# Sheet1.net
KiCad netlist of a schematic drawn in Altium Designer
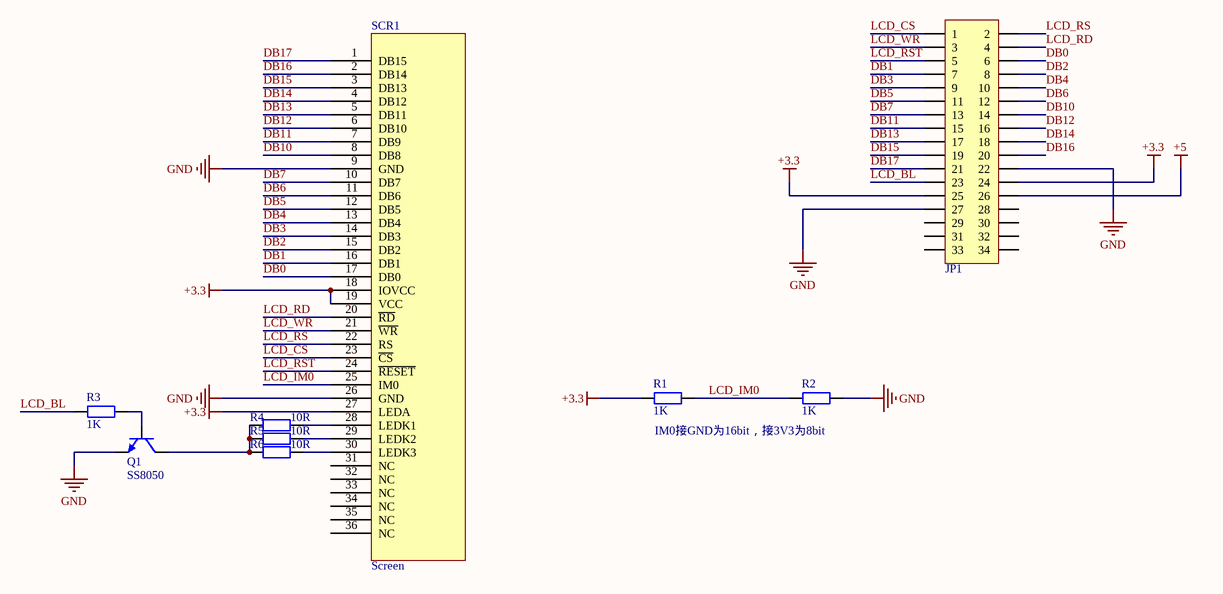
[diagram p0: Sheet1.SchDoc]

(export (version "E")
  (design (tool "Eeschema 10.0.6"))
  (components
    (comp (ref "JP1")
      (value "Header 2X11")
      (footprint "HDR2.54-LI-2x17P")
      (description "17*2P接插件")
      (libsource (lib "5.4 - 接插件-脚距2.54 (100mil) ") (part "Header 17X2"))
    )
    (comp (ref "Q1")
      (value "SS8050")
      (footprint "SOT23-3N")
      (description "高频放大-NPN型")
      (libsource (lib "0.4 - 三极管-场效应管-可控硅") (part "8050-SMD"))
    )
    (comp (ref "R1")
      (value "1K")
      (footprint "R 0603_L")
      (description "贴片电阻")
      (libsource (lib "0.1 - 电阻-电容-电感") (part "R"))
    )
    (comp (ref "R2")
      (value "1K")
      (footprint "R 0603_L")
      (description "贴片电阻")
      (libsource (lib "0.1 - 电阻-电容-电感") (part "R"))
    )
    (comp (ref "R3")
      (value "1K")
      (footprint "R 0603_L")
      (description "贴片电阻")
      (libsource (lib "0.1 - 电阻-电容-电感") (part "R"))
    )
    (comp (ref "R4")
      (value "10R")
      (footprint "R 0603_L")
      (description "贴片电阻")
      (libsource (lib "0.1 - 电阻-电容-电感") (part "R"))
    )
    (comp (ref "R5")
      (value "10R")
      (footprint "R 0603_L")
      (description "贴片电阻")
      (libsource (lib "0.1 - 电阻-电容-电感") (part "R"))
    )
    (comp (ref "R6")
      (value "10R")
      (footprint "R 0603_L")
      (description "贴片电阻")
      (libsource (lib "0.1 - 电阻-电容-电感") (part "R"))
    )
    (comp (ref "SCR1") (value "Screen") (footprint "2.0inLCD") (libsource (lib "Schlib1") (part "2.0inLCD")))
  )
  (nets
    (net (code "1") (name "+3.3") (class "Default")
      (node (ref "JP1") (pin "24") (pinfunction "24_24") (pintype "passive"))
      (node (ref "JP1") (pin "25") (pinfunction "25_25") (pintype "passive"))
      (node (ref "R1") (pin "1") (pinfunction "1_1") (pintype "passive"))
      (node (ref "SCR1") (pin "18") (pinfunction "IOVCC_18") (pintype "passive"))
      (node (ref "SCR1") (pin "19") (pinfunction "VCC_19") (pintype "passive"))
      (node (ref "SCR1") (pin "27") (pinfunction "LEDA_27") (pintype "passive"))
    )
    (net (code "2") (name "+5") (class "Default")
      (node (ref "JP1") (pin "26") (pinfunction "26_26") (pintype "passive"))
    )
    (net (code "3") (name "/DB0") (class "Default")
      (node (ref "JP1") (pin "6") (pinfunction "6_6") (pintype "passive"))
      (node (ref "SCR1") (pin "17") (pinfunction "DB0_17") (pintype "passive"))
    )
    (net (code "4") (name "/DB1") (class "Default")
      (node (ref "JP1") (pin "7") (pinfunction "7_7") (pintype "passive"))
      (node (ref "SCR1") (pin "16") (pinfunction "DB1_16") (pintype "passive"))
    )
    (net (code "5") (name "/DB2") (class "Default")
      (node (ref "JP1") (pin "8") (pinfunction "8_8") (pintype "passive"))
      (node (ref "SCR1") (pin "15") (pinfunction "DB2_15") (pintype "passive"))
    )
    (net (code "6") (name "/DB3") (class "Default")
      (node (ref "JP1") (pin "9") (pinfunction "9_9") (pintype "passive"))
      (node (ref "SCR1") (pin "14") (pinfunction "DB3_14") (pintype "passive"))
    )
    (net (code "7") (name "/DB4") (class "Default")
      (node (ref "JP1") (pin "10") (pinfunction "10_10") (pintype "passive"))
      (node (ref "SCR1") (pin "13") (pinfunction "DB4_13") (pintype "passive"))
    )
    (net (code "8") (name "/DB5") (class "Default")
      (node (ref "JP1") (pin "11") (pinfunction "11_11") (pintype "passive"))
      (node (ref "SCR1") (pin "12") (pinfunction "DB5_12") (pintype "passive"))
    )
    (net (code "9") (name "/DB6") (class "Default")
      (node (ref "JP1") (pin "12") (pinfunction "12_12") (pintype "passive"))
      (node (ref "SCR1") (pin "11") (pinfunction "DB6_11") (pintype "passive"))
    )
    (net (code "10") (name "/DB7") (class "Default")
      (node (ref "JP1") (pin "13") (pinfunction "13_13") (pintype "passive"))
      (node (ref "SCR1") (pin "10") (pinfunction "DB7_10") (pintype "passive"))
    )
    (net (code "11") (name "/DB10") (class "Default")
      (node (ref "JP1") (pin "14") (pinfunction "14_14") (pintype "passive"))
      (node (ref "SCR1") (pin "8") (pinfunction "DB8_8") (pintype "passive"))
    )
    (net (code "12") (name "/DB11") (class "Default")
      (node (ref "JP1") (pin "15") (pinfunction "15_15") (pintype "passive"))
      (node (ref "SCR1") (pin "7") (pinfunction "DB9_7") (pintype "passive"))
    )
    (net (code "13") (name "/DB12") (class "Default")
      (node (ref "JP1") (pin "16") (pinfunction "16_16") (pintype "passive"))
      (node (ref "SCR1") (pin "6") (pinfunction "DB10_6") (pintype "passive"))
    )
    (net (code "14") (name "/DB13") (class "Default")
      (node (ref "JP1") (pin "17") (pinfunction "17_17") (pintype "passive"))
      (node (ref "SCR1") (pin "5") (pinfunction "DB11_5") (pintype "passive"))
    )
    (net (code "15") (name "/DB14") (class "Default")
      (node (ref "JP1") (pin "18") (pinfunction "18_18") (pintype "passive"))
      (node (ref "SCR1") (pin "4") (pinfunction "DB12_4") (pintype "passive"))
    )
    (net (code "16") (name "/DB15") (class "Default")
      (node (ref "JP1") (pin "19") (pinfunction "19_19") (pintype "passive"))
      (node (ref "SCR1") (pin "3") (pinfunction "DB13_3") (pintype "passive"))
    )
    (net (code "17") (name "/DB16") (class "Default")
      (node (ref "JP1") (pin "20") (pinfunction "20_20") (pintype "passive"))
      (node (ref "SCR1") (pin "2") (pinfunction "DB14_2") (pintype "passive"))
    )
    (net (code "18") (name "/DB17") (class "Default")
      (node (ref "JP1") (pin "21") (pinfunction "21_21") (pintype "passive"))
      (node (ref "SCR1") (pin "1") (pinfunction "DB15_1") (pintype "passive"))
    )
    (net (code "19") (name "/LCD_BL") (class "Default")
      (node (ref "JP1") (pin "23") (pinfunction "23_23") (pintype "passive"))
      (node (ref "R3") (pin "1") (pinfunction "1_1") (pintype "passive"))
    )
    (net (code "20") (name "/LCD_CS") (class "Default")
      (node (ref "JP1") (pin "1") (pinfunction "1_1") (pintype "passive"))
      (node (ref "SCR1") (pin "23") (pinfunction "~{CS}_23") (pintype "passive"))
    )
    (net (code "21") (name "/LCD_IM0") (class "Default")
      (node (ref "R1") (pin "2") (pinfunction "2_2") (pintype "passive"))
      (node (ref "R2") (pin "1") (pinfunction "1_1") (pintype "passive"))
      (node (ref "SCR1") (pin "25") (pinfunction "IM0_25") (pintype "passive"))
    )
    (net (code "22") (name "/LCD_RD") (class "Default")
      (node (ref "JP1") (pin "4") (pinfunction "4_4") (pintype "passive"))
      (node (ref "SCR1") (pin "20") (pinfunction "~{RD}_20") (pintype "passive"))
    )
    (net (code "23") (name "/LCD_RS") (class "Default")
      (node (ref "JP1") (pin "2") (pinfunction "2_2") (pintype "passive"))
      (node (ref "SCR1") (pin "22") (pinfunction "RS_22") (pintype "passive"))
    )
    (net (code "24") (name "/LCD_RST") (class "Default")
      (node (ref "JP1") (pin "5") (pinfunction "5_5") (pintype "passive"))
      (node (ref "SCR1") (pin "24") (pinfunction "~{RESET}_24") (pintype "passive"))
    )
    (net (code "25") (name "/LCD_WR") (class "Default")
      (node (ref "JP1") (pin "3") (pinfunction "3_3") (pintype "passive"))
      (node (ref "SCR1") (pin "21") (pinfunction "~{WR}_21") (pintype "passive"))
    )
    (net (code "26") (name "GND") (class "Default")
      (node (ref "JP1") (pin "22") (pinfunction "22_22") (pintype "passive"))
      (node (ref "JP1") (pin "27") (pinfunction "27_27") (pintype "passive"))
      (node (ref "Q1") (pin "2") (pinfunction "E_2") (pintype "passive"))
      (node (ref "R2") (pin "2") (pinfunction "2_2") (pintype "passive"))
      (node (ref "SCR1") (pin "26") (pinfunction "GND_26") (pintype "passive"))
      (node (ref "SCR1") (pin "9") (pinfunction "GND_9") (pintype "passive"))
    )
    (net (code "27") (name "Net-(Q1-B)") (class "Default")
      (node (ref "Q1") (pin "1") (pinfunction "B_1") (pintype "passive"))
      (node (ref "R3") (pin "2") (pinfunction "2_2") (pintype "passive"))
    )
    (net (code "28") (name "Net-(Q1-C)") (class "Default")
      (node (ref "Q1") (pin "3") (pinfunction "C_3") (pintype "passive"))
      (node (ref "R4") (pin "1") (pinfunction "1_1") (pintype "passive"))
      (node (ref "R5") (pin "1") (pinfunction "1_1") (pintype "passive"))
      (node (ref "R6") (pin "1") (pinfunction "1_1") (pintype "passive"))
    )
    (net (code "29") (name "Net-(SCR1-LEDK1)") (class "Default")
      (node (ref "R4") (pin "2") (pinfunction "2_2") (pintype "passive"))
      (node (ref "SCR1") (pin "28") (pinfunction "LEDK1_28") (pintype "passive"))
    )
    (net (code "30") (name "Net-(SCR1-LEDK2)") (class "Default")
      (node (ref "R5") (pin "2") (pinfunction "2_2") (pintype "passive"))
      (node (ref "SCR1") (pin "29") (pinfunction "LEDK2_29") (pintype "passive"))
    )
    (net (code "31") (name "Net-(SCR1-LEDK3)") (class "Default")
      (node (ref "R6") (pin "2") (pinfunction "2_2") (pintype "passive"))
      (node (ref "SCR1") (pin "30") (pinfunction "LEDK3_30") (pintype "passive"))
    )
    (net (code "32") (name "unconnected-(JP1-Pad28)") (class "Default")
      (node (ref "JP1") (pin "28") (pinfunction "28_28") (pintype "passive"))
    )
    (net (code "33") (name "unconnected-(JP1-Pad29)") (class "Default")
      (node (ref "JP1") (pin "29") (pinfunction "29_29") (pintype "passive"))
    )
    (net (code "34") (name "unconnected-(JP1-Pad30)") (class "Default")
      (node (ref "JP1") (pin "30") (pinfunction "30_30") (pintype "passive"))
    )
    (net (code "35") (name "unconnected-(JP1-Pad31)") (class "Default")
      (node (ref "JP1") (pin "31") (pinfunction "31_31") (pintype "passive"))
    )
    (net (code "36") (name "unconnected-(JP1-Pad32)") (class "Default")
      (node (ref "JP1") (pin "32") (pinfunction "32_32") (pintype "passive"))
    )
    (net (code "37") (name "unconnected-(JP1-Pad33)") (class "Default")
      (node (ref "JP1") (pin "33") (pinfunction "33_33") (pintype "passive"))
    )
    (net (code "38") (name "unconnected-(JP1-Pad34)") (class "Default")
      (node (ref "JP1") (pin "34") (pinfunction "34_34") (pintype "passive"))
    )
    (net (code "39") (name "unconnected-(SCR1-NC-Pad31)") (class "Default")
      (node (ref "SCR1") (pin "31") (pinfunction "NC_31") (pintype "passive"))
    )
    (net (code "40") (name "unconnected-(SCR1-NC-Pad32)") (class "Default")
      (node (ref "SCR1") (pin "32") (pinfunction "NC_32") (pintype "passive"))
    )
    (net (code "41") (name "unconnected-(SCR1-NC-Pad33)") (class "Default")
      (node (ref "SCR1") (pin "33") (pinfunction "NC_33") (pintype "passive"))
    )
    (net (code "42") (name "unconnected-(SCR1-NC-Pad34)") (class "Default")
      (node (ref "SCR1") (pin "34") (pinfunction "NC_34") (pintype "passive"))
    )
    (net (code "43") (name "unconnected-(SCR1-NC-Pad35)") (class "Default")
      (node (ref "SCR1") (pin "35") (pinfunction "NC_35") (pintype "passive"))
    )
    (net (code "44") (name "unconnected-(SCR1-NC-Pad36)") (class "Default")
      (node (ref "SCR1") (pin "36") (pinfunction "NC_36") (pintype "passive"))
    )
  )
)
